# MicrocontrollerModule.net
KiCad netlist of a schematic drawn in EAGLE
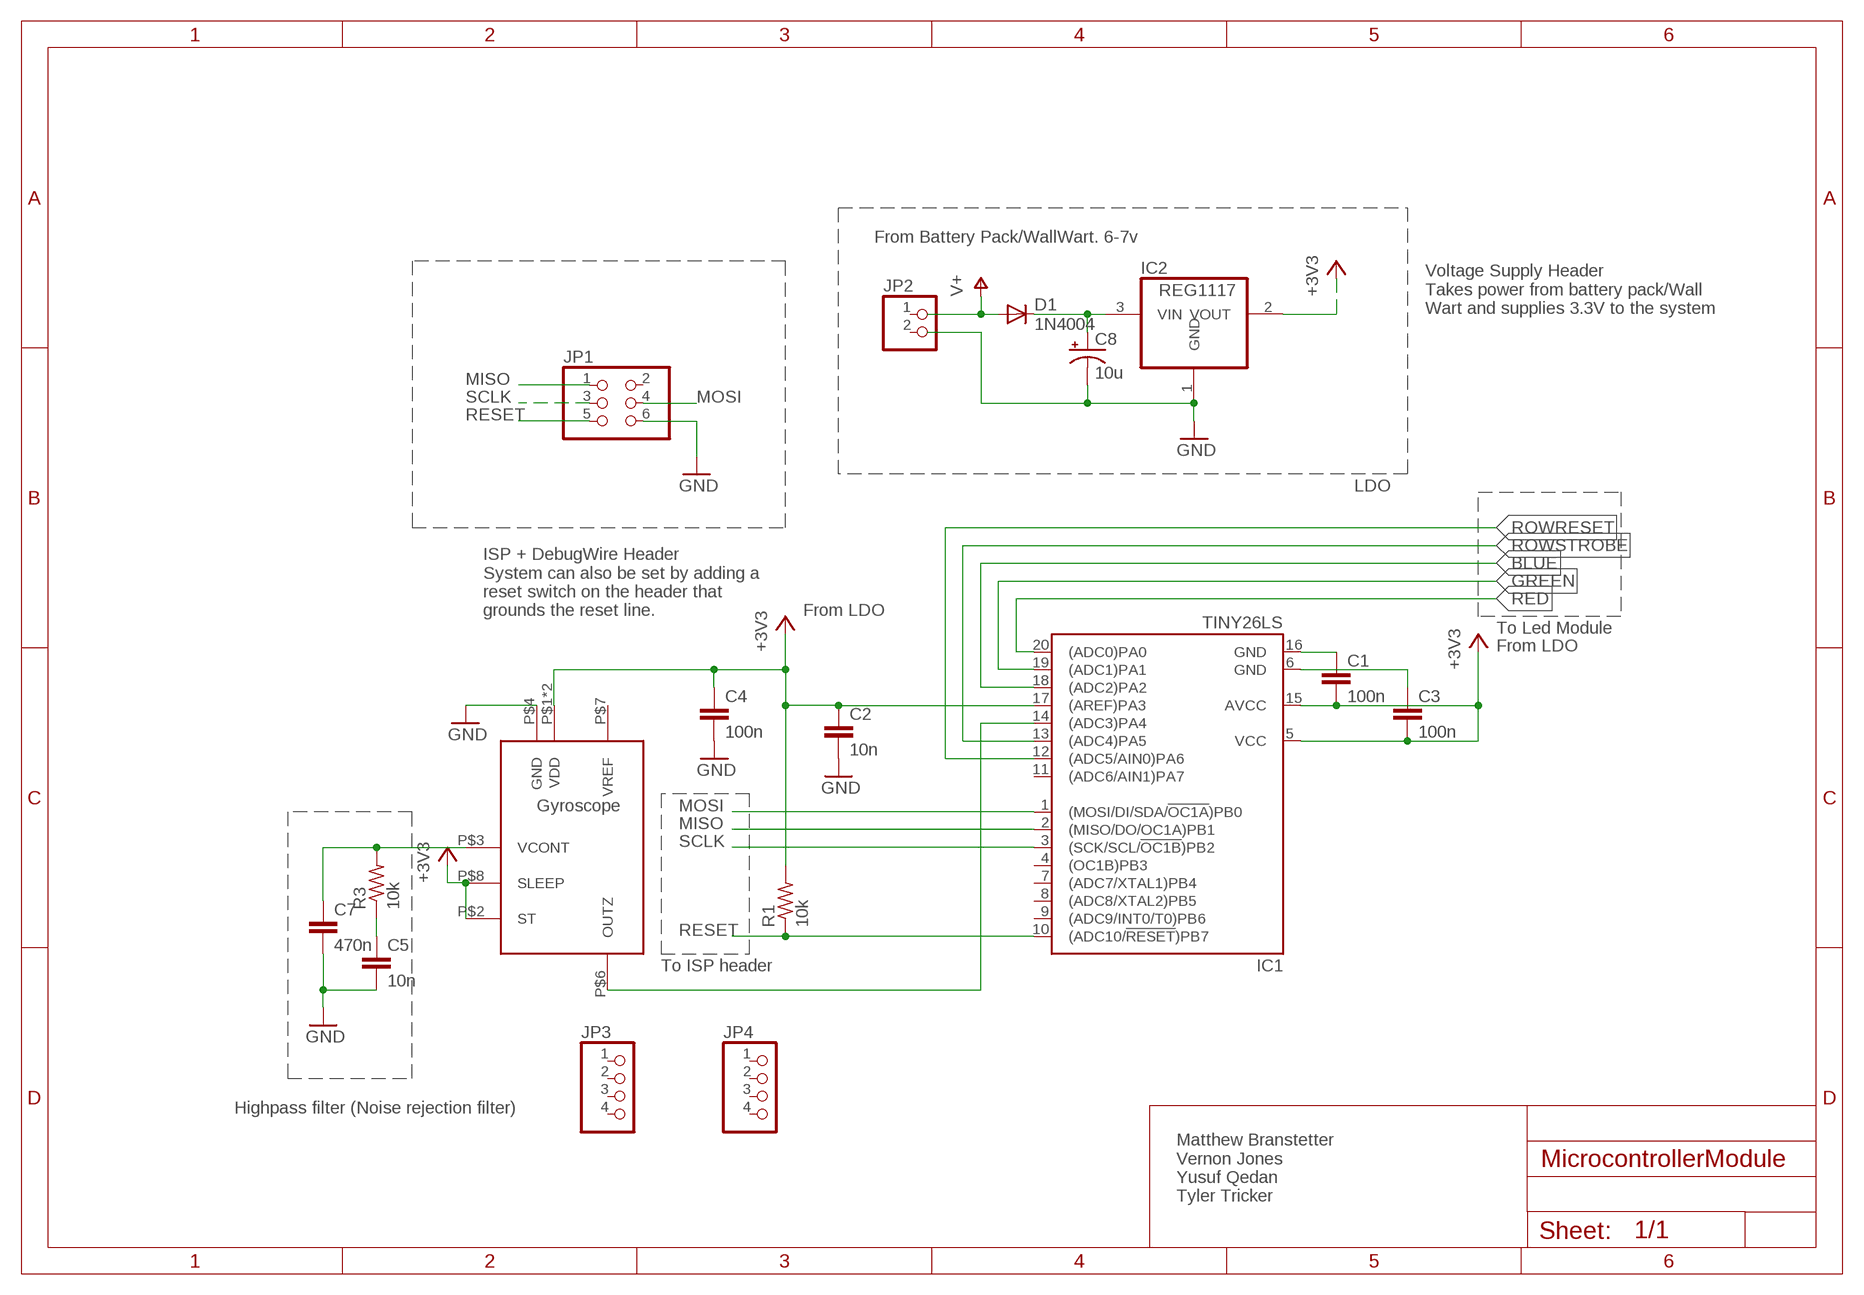
[diagram p0: schematic, sheet 1]

(export (version "E")
  (design (tool "Eeschema 10.0.6"))
  (components
    (comp (ref "C1")
      (value "100n")
      (footprint "eagle-import:C1210")
      (libsource (lib "eagle-import") (part "C-EUC1210"))
    )
    (comp (ref "C2")
      (value "10n")
      (footprint "eagle-import:C1210")
      (libsource (lib "eagle-import") (part "C-EUC1210"))
    )
    (comp (ref "C3")
      (value "100n")
      (footprint "eagle-import:C1210")
      (libsource (lib "eagle-import") (part "C-EUC1210"))
    )
    (comp (ref "C4")
      (value "100n")
      (footprint "eagle-import:C1210")
      (libsource (lib "eagle-import") (part "C-EUC1210"))
    )
    (comp (ref "C5")
      (value "10n")
      (footprint "eagle-import:C1210")
      (libsource (lib "eagle-import") (part "C-EUC1210"))
    )
    (comp (ref "C7")
      (value "470n")
      (footprint "eagle-import:C1210")
      (libsource (lib "eagle-import") (part "C-EUC1210"))
    )
    (comp (ref "C8")
      (value "10u")
      (footprint "eagle-import:153CLV-0605")
      (libsource (lib "eagle-import") (part "CPOL-US153CLV-0605"))
    )
    (comp (ref "D1")
      (value "1N4004")
      (footprint "eagle-import:DO41-10")
      (libsource (lib "eagle-import") (part "1N4004"))
    )
    (comp (ref "IC1")
      (value "TINY26LS")
      (footprint "eagle-import:SO20L")
      (fields (field (name "MPN") "ATTINY26L-8SU"))
      (libsource (lib "eagle-import") (part "TINY26SL"))
    )
    (comp (ref "IC2")
      (value "REG1117")
      (footprint "eagle-import:SOT223")
      (libsource (lib "eagle-import") (part "REG1117"))
    )
    (comp (ref "JP1")
      (value "PINHD-2X3")
      (footprint "eagle-import:2X03")
      (libsource (lib "eagle-import") (part "PINHD-2X3"))
    )
    (comp (ref "JP2")
      (value "PINHD-1X2")
      (footprint "eagle-import:1X02")
      (libsource (lib "eagle-import") (part "PINHD-1X2"))
    )
    (comp (ref "JP3")
      (value "PINHD-1X4")
      (footprint "eagle-import:1X04")
      (libsource (lib "eagle-import") (part "PINHD-1X4"))
    )
    (comp (ref "JP4")
      (value "PINHD-1X4")
      (footprint "eagle-import:1X04")
      (libsource (lib "eagle-import") (part "PINHD-1X4"))
    )
    (comp (ref "R1")
      (value "10k")
      (footprint "eagle-import:M2012")
      (libsource (lib "eagle-import") (part "R-US_M2012"))
    )
    (comp (ref "R3")
      (value "10k")
      (footprint "eagle-import:M2012")
      (libsource (lib "eagle-import") (part "R-US_M2012"))
    )
    (comp (ref "U$1")
      (value "LY3200ALHLY3200ALH-LGA10")
      (footprint "eagle-import:LGA10")
      (libsource (lib "eagle-import") (part "LY3200ALHLY3200ALH-LGA10"))
    )
  )
  (nets
    (net (code "1") (name "+3V3") (class "Default")
      (node (ref "C1") (pin "2") (pinfunction "2_2") (pintype "passive"))
      (node (ref "C2") (pin "1") (pinfunction "1_1") (pintype "passive"))
      (node (ref "C3") (pin "2") (pinfunction "2_2") (pintype "passive"))
      (node (ref "C4") (pin "1") (pinfunction "1_1") (pintype "passive"))
      (node (ref "IC1") (pin "15") (pinfunction "AVCC_15") (pintype "power_in"))
      (node (ref "IC1") (pin "17") (pinfunction "(AREF)PA3_17") (pintype "bidirectional"))
      (node (ref "IC1") (pin "5") (pinfunction "VCC_5") (pintype "power_in"))
      (node (ref "IC2") (pin "2") (pinfunction "VOUT_2") (pintype "output"))
      (node (ref "R1") (pin "2") (pinfunction "2_2") (pintype "passive"))
      (node (ref "U$1") (pin "P$1") (pinfunction "VDD_P$1") (pintype "power_in"))
      (node (ref "U$1") (pin "P$2") (pinfunction "ST_P$2") (pintype "input"))
      (node (ref "U$1") (pin "P$8") (pinfunction "SLEEP_P$8") (pintype "input"))
      (node (ref "U$1") (pin "P$9") (pinfunction "VDD_P$9") (pintype "power_in"))
    )
    (net (code "2") (name "/MISO") (class "Default")
      (node (ref "IC1") (pin "2") (pinfunction "(MISO/DO/OC1A)PB1_2") (pintype "bidirectional"))
      (node (ref "JP1") (pin "1") (pinfunction "1_1") (pintype "passive"))
    )
    (net (code "3") (name "/MOSI") (class "Default")
      (node (ref "IC1") (pin "1") (pinfunction "(MOSI/DI/SDA/~{OC1A})PB0_1") (pintype "bidirectional"))
      (node (ref "JP1") (pin "4") (pinfunction "4_4") (pintype "passive"))
    )
    (net (code "4") (name "/RESET") (class "Default")
      (node (ref "IC1") (pin "10") (pinfunction "(ADC10/~{RESET})PB7_10") (pintype "bidirectional"))
      (node (ref "JP1") (pin "5") (pinfunction "5_5") (pintype "passive"))
      (node (ref "R1") (pin "1") (pinfunction "1_1") (pintype "passive"))
    )
    (net (code "5") (name "/SCLK") (class "Default")
      (node (ref "IC1") (pin "3") (pinfunction "(SCK/SCL/~{OC1B})PB2_3") (pintype "bidirectional"))
      (node (ref "JP1") (pin "3") (pinfunction "3_3") (pintype "passive"))
    )
    (net (code "6") (name "BLUE") (class "Default")
      (node (ref "IC1") (pin "18") (pinfunction "(ADC2)PA2_18") (pintype "bidirectional"))
    )
    (net (code "7") (name "GND") (class "Default")
      (node (ref "C2") (pin "2") (pinfunction "2_2") (pintype "passive"))
      (node (ref "C4") (pin "2") (pinfunction "2_2") (pintype "passive"))
      (node (ref "C5") (pin "2") (pinfunction "2_2") (pintype "passive"))
      (node (ref "C7") (pin "2") (pinfunction "2_2") (pintype "passive"))
      (node (ref "C8") (pin "-") (pinfunction "-_-") (pintype "passive"))
      (node (ref "IC2") (pin "1") (pinfunction "GND_1") (pintype "power_in"))
      (node (ref "JP1") (pin "6") (pinfunction "6_6") (pintype "passive"))
      (node (ref "U$1") (pin "P$4") (pinfunction "GND_P$4") (pintype "power_in"))
    )
    (net (code "8") (name "GREEN") (class "Default")
      (node (ref "IC1") (pin "19") (pinfunction "(ADC1)PA1_19") (pintype "bidirectional"))
    )
    (net (code "9") (name "Net-(C1-Pad1)") (class "Default")
      (node (ref "C1") (pin "1") (pinfunction "1_1") (pintype "passive"))
      (node (ref "IC1") (pin "16") (pinfunction "GND_16") (pintype "power_in"))
    )
    (net (code "10") (name "Net-(C3-Pad1)") (class "Default")
      (node (ref "C3") (pin "1") (pinfunction "1_1") (pintype "passive"))
      (node (ref "IC1") (pin "6") (pinfunction "GND_6") (pintype "power_in"))
    )
    (net (code "11") (name "Net-(C5-Pad1)") (class "Default")
      (node (ref "C5") (pin "1") (pinfunction "1_1") (pintype "passive"))
      (node (ref "R3") (pin "1") (pinfunction "1_1") (pintype "passive"))
    )
    (net (code "12") (name "Net-(IC1-(ADC3)PA4)") (class "Default")
      (node (ref "IC1") (pin "14") (pinfunction "(ADC3)PA4_14") (pintype "bidirectional"))
      (node (ref "U$1") (pin "P$6") (pinfunction "OUTZ_P$6") (pintype "output"))
    )
    (net (code "13") (name "Net-(IC2-VIN)") (class "Default")
      (node (ref "C8") (pin "+") (pinfunction "+_+") (pintype "passive"))
      (node (ref "D1") (pin "C") (pinfunction "C_C") (pintype "passive"))
      (node (ref "IC2") (pin "3") (pinfunction "VIN_3") (pintype "input"))
    )
    (net (code "14") (name "Net-(U$1-VCONT)") (class "Default")
      (node (ref "C7") (pin "1") (pinfunction "1_1") (pintype "passive"))
      (node (ref "R3") (pin "2") (pinfunction "2_2") (pintype "passive"))
      (node (ref "U$1") (pin "P$3") (pinfunction "VCONT_P$3") (pintype "input"))
    )
    (net (code "15") (name "RED") (class "Default")
      (node (ref "IC1") (pin "20") (pinfunction "(ADC0)PA0_20") (pintype "bidirectional"))
    )
    (net (code "16") (name "ROWRESET") (class "Default")
      (node (ref "IC1") (pin "12") (pinfunction "(ADC5/AIN0)PA6_12") (pintype "bidirectional"))
    )
    (net (code "17") (name "ROWSTROBE") (class "Default")
      (node (ref "IC1") (pin "13") (pinfunction "(ADC4)PA5_13") (pintype "bidirectional"))
    )
    (net (code "18") (name "V+") (class "Default")
      (node (ref "D1") (pin "A") (pinfunction "A_A") (pintype "passive"))
    )
    (net (code "19") (name "unconnected-(IC1-(ADC6{slash}AIN1)PA7-Pad11)") (class "Default")
      (node (ref "IC1") (pin "11") (pinfunction "(ADC6/AIN1)PA7_11") (pintype "bidirectional"))
    )
    (net (code "20") (name "unconnected-(IC1-(ADC7{slash}XTAL1)PB4-Pad7)") (class "Default")
      (node (ref "IC1") (pin "7") (pinfunction "(ADC7/XTAL1)PB4_7") (pintype "bidirectional"))
    )
    (net (code "21") (name "unconnected-(IC1-(ADC8{slash}XTAL2)PB5-Pad8)") (class "Default")
      (node (ref "IC1") (pin "8") (pinfunction "(ADC8/XTAL2)PB5_8") (pintype "bidirectional"))
    )
    (net (code "22") (name "unconnected-(IC1-(ADC9{slash}INT0{slash}T0)PB6-Pad9)") (class "Default")
      (node (ref "IC1") (pin "9") (pinfunction "(ADC9/INT0/T0)PB6_9") (pintype "bidirectional"))
    )
    (net (code "23") (name "unconnected-(IC1-(OC1B)PB3-Pad4)") (class "Default")
      (node (ref "IC1") (pin "4") (pinfunction "(OC1B)PB3_4") (pintype "bidirectional"))
    )
    (net (code "24") (name "unconnected-(JP1-Pad2)") (class "Default")
      (node (ref "JP1") (pin "2") (pinfunction "2_2") (pintype "passive"))
    )
    (net (code "25") (name "unconnected-(JP2-Pad1)") (class "Default")
      (node (ref "JP2") (pin "1") (pinfunction "1_1") (pintype "passive"))
    )
    (net (code "26") (name "unconnected-(JP2-Pad2)") (class "Default")
      (node (ref "JP2") (pin "2") (pinfunction "2_2") (pintype "passive"))
    )
    (net (code "27") (name "unconnected-(JP3-Pad1)") (class "Default")
      (node (ref "JP3") (pin "1") (pinfunction "1_1") (pintype "passive"))
    )
    (net (code "28") (name "unconnected-(JP3-Pad2)") (class "Default")
      (node (ref "JP3") (pin "2") (pinfunction "2_2") (pintype "passive"))
    )
    (net (code "29") (name "unconnected-(JP3-Pad3)") (class "Default")
      (node (ref "JP3") (pin "3") (pinfunction "3_3") (pintype "passive"))
    )
    (net (code "30") (name "unconnected-(JP3-Pad4)") (class "Default")
      (node (ref "JP3") (pin "4") (pinfunction "4_4") (pintype "passive"))
    )
    (net (code "31") (name "unconnected-(JP4-Pad1)") (class "Default")
      (node (ref "JP4") (pin "1") (pinfunction "1_1") (pintype "passive"))
    )
    (net (code "32") (name "unconnected-(JP4-Pad2)") (class "Default")
      (node (ref "JP4") (pin "2") (pinfunction "2_2") (pintype "passive"))
    )
    (net (code "33") (name "unconnected-(JP4-Pad3)") (class "Default")
      (node (ref "JP4") (pin "3") (pinfunction "3_3") (pintype "passive"))
    )
    (net (code "34") (name "unconnected-(JP4-Pad4)") (class "Default")
      (node (ref "JP4") (pin "4") (pinfunction "4_4") (pintype "passive"))
    )
    (net (code "35") (name "unconnected-(U$1-VREF-PadP$7)") (class "Default")
      (node (ref "U$1") (pin "P$7") (pinfunction "VREF_P$7") (pintype "input"))
    )
  )
)
